# USB_Sheet.net
KiCad netlist of a schematic drawn in Altium Designer
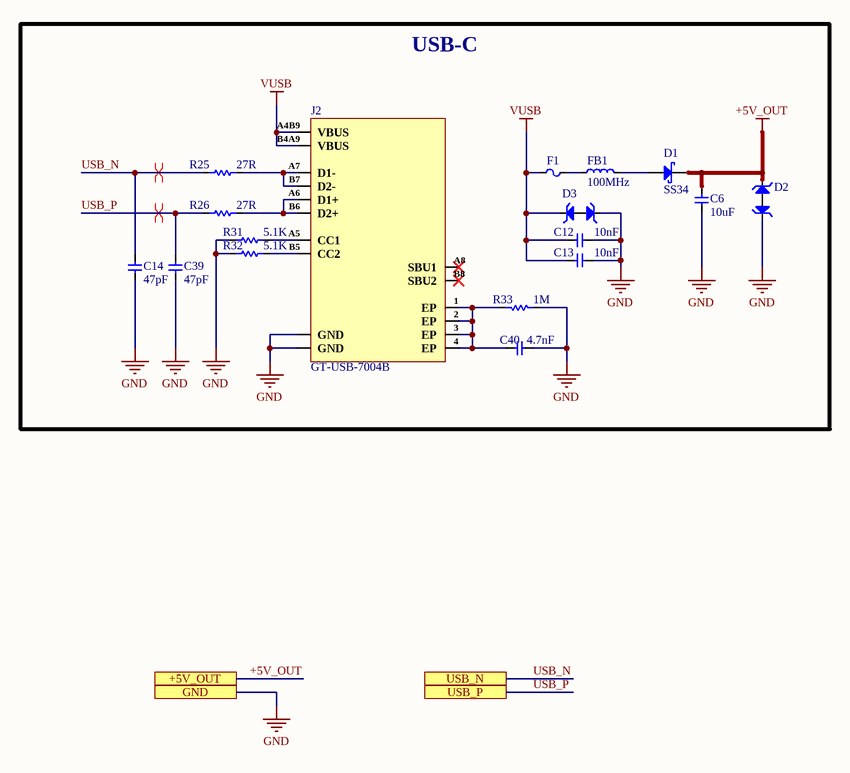
[diagram p0: USB_Sheet.SchDoc]

(export (version "E")
  (design (tool "Eeschema 10.0.6"))
  (components
    (comp (ref "C6")
      (value "10uF")
      (footprint "Cap-0603")
      (description "CAP CER 10UF 25V X5R 0603")
      (fields
        (field (name "MANUFACTURER") "Samsung")
        (field (name "MANUFACTURER PART NUMBER") "CL10A106MA8NRNC")
      )
      (libsource (lib "eSpark Libraries") (part "CL10A106MA8NRNC"))
    )
    (comp (ref "C12")
      (value "10nF")
      (footprint "Cap-0402")
      (description "CAP CER 10000PF 25V X7R 0402")
      (fields
        (field (name "MANUFACTURER") "Yageo")
        (field (name "MANUFACTURER PART NUMBER") "CC0402KRX7R8BB103")
      )
      (libsource (lib "eSpark Libraries") (part "CC0402KRX7R8BB103"))
    )
    (comp (ref "C13")
      (value "10nF")
      (footprint "Cap-0402")
      (description "CAP CER 10000PF 25V X7R 0402")
      (fields
        (field (name "MANUFACTURER") "Yageo")
        (field (name "MANUFACTURER PART NUMBER") "CC0402KRX7R8BB103")
      )
      (libsource (lib "eSpark Libraries") (part "CC0402KRX7R8BB103"))
    )
    (comp (ref "C14")
      (value "47pF")
      (footprint "Cap-0402")
      (description "CAP CER 47PF 50V C0G/NP0 0402")
      (fields
        (field (name "MANUFACTURER") "Murata")
        (field (name "MANUFACTURER PART NUMBER") "GCM1555C1H470FA16D")
      )
      (libsource (lib "eSpark Libraries") (part "GCM1555C1H470FA16D"))
    )
    (comp (ref "C39")
      (value "47pF")
      (footprint "Cap-0402")
      (description "CAP CER 47PF 50V C0G/NP0 0402")
      (fields
        (field (name "MANUFACTURER") "Murata")
        (field (name "MANUFACTURER PART NUMBER") "GCM1555C1H470FA16D")
      )
      (libsource (lib "eSpark Libraries") (part "GCM1555C1H470FA16D"))
    )
    (comp (ref "C40")
      (value "4.7nF")
      (footprint "Cap-0402")
      (description "CAP CER 4700PF 50V X7R 0402")
      (fields
        (field (name "MANUFACTURER") "Yageo")
        (field (name "MANUFACTURER PART NUMBER") "CC0402KRX7R9BB472")
      )
      (libsource (lib "eSpark Libraries") (part "CC0402KRX7R9BB472"))
    )
    (comp (ref "D1")
      (value "SS34")
      (footprint "SMA")
      (description "0.5mA@40V 40V Single 3A 0.55V@3A SMA(DO-214AC) Schottky Barrier Diodes (SBD) ROHS")
      (fields (field (name "MANUFACTURER") "MDD") (field (name "LCSC PART NUMBER") "C8678"))
      (libsource (lib "eSpark Libraries") (part "SS34"))
    )
    (comp (ref "D2")
      (value "PESD5V0H1BSFYL")
      (footprint "DSN0603-2")
      (description "TVS DIODE 5VWM 6.3VC DSN0603-2")
      (fields (field (name "MANUFACTURER") "Nexperia") (field (name "LCSC PART NUMBER") "C477989"))
      (libsource (lib "eSpark Libraries") (part "PESD5V0H1BSFYL"))
    )
    (comp (ref "D3")
      (value "PESD5V0H1BSFYL")
      (footprint "DSN0603-2")
      (description "TVS DIODE 5VWM 6.3VC DSN0603-2")
      (fields (field (name "MANUFACTURER") "Nexperia") (field (name "LCSC PART NUMBER") "C477989"))
      (libsource (lib "eSpark Libraries") (part "PESD5V0H1BSFYL"))
    )
    (comp (ref "F1")
      (value "BSMD0805L-300")
      (footprint "Fuse-0805")
      (description "6V 3A 50A 1W -40℃~+85℃ 6A 3mΩ 5s 30mΩ 0805 Resettable Fuses ROHS")
      (fields (field (name "MANUFACTURER") "BHFUSE") (field (name "LCSC PART NUMBER") "C2757932"))
      (libsource (lib "eSpark Libraries") (part "BSMD0805L-300"))
    )
    (comp (ref "FB1")
      (value "100MHz")
      (footprint "IND-1206")
      (description "FERRITE BEAD 120 OHM 1206 1LN")
      (fields
        (field (name "MANUFACTURER") "Murata")
        (field (name "MANUFACTURER PART NUMBER") "BLM31PG121SN1L")
      )
      (libsource (lib "eSpark Libraries") (part "BLM31PG121SN1L"))
    )
    (comp (ref "J2")
      (value "GT-USB-7004B")
      (footprint "GT-USB-7004B")
      (description "USB-C (USB TYPE-C) Receptacle Connector 16 Position Surface Mount, Right Angle")
      (fields (field (name "MANUFACTURER") "G-Switch") (field (name "LCSC PART NUMBER") "C5368946"))
      (libsource (lib "eSpark Libraries") (part "GT-USB-7004B"))
    )
    (comp (ref "R25")
      (value "27R")
      (footprint "Res-0402")
      (description "62.5mW Thick Film Resistors 50V ±100ppm/℃ ±1% 27Ω 0402 Chip Resistor - Surface Mount ROHS")
      (fields
        (field (name "MANUFACTURER") "YAGEO")
        (field (name "MANUFACTURER PART NUMBER") "RC0402FR-0727RL")
      )
      (libsource (lib "eSpark Libraries") (part "RC0402FR-0727RL"))
    )
    (comp (ref "R26")
      (value "27R")
      (footprint "Res-0402")
      (description "62.5mW Thick Film Resistors 50V ±100ppm/℃ ±1% 27Ω 0402 Chip Resistor - Surface Mount ROHS")
      (fields
        (field (name "MANUFACTURER") "YAGEO")
        (field (name "MANUFACTURER PART NUMBER") "RC0402FR-0727RL")
      )
      (libsource (lib "eSpark Libraries") (part "RC0402FR-0727RL"))
    )
    (comp (ref "R31")
      (value "5.1K")
      (footprint "Res-0402")
      (description "RES 5.1K OHM 1% 1/16W 0402")
      (fields
        (field (name "MANUFACTURER") "Yageo")
        (field (name "MANUFACTURER PART NUMBER") "RC0402FR-075K1L")
      )
      (libsource (lib "eSpark Libraries") (part "RC0402FR-075K1L"))
    )
    (comp (ref "R32")
      (value "5.1K")
      (footprint "Res-0402")
      (description "RES 5.1K OHM 1% 1/16W 0402")
      (fields
        (field (name "MANUFACTURER") "Yageo")
        (field (name "MANUFACTURER PART NUMBER") "RC0402FR-075K1L")
      )
      (libsource (lib "eSpark Libraries") (part "RC0402FR-075K1L"))
    )
    (comp (ref "R33")
      (value "1M")
      (footprint "Res-0402")
      (description "RES SMD 1M OHM 5% 1/16W 0402")
      (fields
        (field (name "MANUFACTURER") "Yageo")
        (field (name "MANUFACTURER PART NUMBER") "AF0402JR-071ML")
      )
      (libsource (lib "eSpark Libraries") (part "AF0402JR-071ML"))
    )
  )
  (nets
    (net (code "1") (name "+5V_OUT") (class "Default")
      (node (ref "C6") (pin "2") (pinfunction "2_2") (pintype "passive"))
      (node (ref "D1") (pin "1") (pinfunction "K_1") (pintype "passive"))
      (node (ref "D2") (pin "2") (pinfunction "2_2") (pintype "passive"))
    )
    (net (code "2") (name "/USB_N") (class "Default")
      (node (ref "C14") (pin "2") (pinfunction "2_2") (pintype "passive"))
      (node (ref "R25") (pin "1") (pinfunction "1_1") (pintype "passive"))
    )
    (net (code "3") (name "/USB_P") (class "Default")
      (node (ref "C39") (pin "2") (pinfunction "2_2") (pintype "passive"))
      (node (ref "R26") (pin "1") (pinfunction "1_1") (pintype "passive"))
    )
    (net (code "4") (name "GND") (class "Default")
      (node (ref "C12") (pin "2") (pinfunction "2_2") (pintype "passive"))
      (node (ref "C13") (pin "2") (pinfunction "2_2") (pintype "passive"))
      (node (ref "C14") (pin "1") (pinfunction "1_1") (pintype "passive"))
      (node (ref "C39") (pin "1") (pinfunction "1_1") (pintype "passive"))
      (node (ref "C40") (pin "1") (pinfunction "1_1") (pintype "passive"))
      (node (ref "C6") (pin "1") (pinfunction "1_1") (pintype "passive"))
      (node (ref "D2") (pin "1") (pinfunction "1_1") (pintype "passive"))
      (node (ref "D3") (pin "2") (pinfunction "2_2") (pintype "passive"))
      (node (ref "J2") (pin "A1B12") (pinfunction "GND_A1B12") (pintype "passive"))
      (node (ref "J2") (pin "B1A12") (pinfunction "GND_B1A12") (pintype "passive"))
      (node (ref "R31") (pin "1") (pinfunction "1_1") (pintype "passive"))
      (node (ref "R32") (pin "1") (pinfunction "1_1") (pintype "passive"))
      (node (ref "R33") (pin "1") (pinfunction "1_1") (pintype "passive"))
    )
    (net (code "5") (name "Net-(C40-Pad2)") (class "Default")
      (node (ref "C40") (pin "2") (pinfunction "2_2") (pintype "passive"))
      (node (ref "J2") (pin "1") (pinfunction "EP_1") (pintype "passive"))
      (node (ref "J2") (pin "2") (pinfunction "EP_2") (pintype "passive"))
      (node (ref "J2") (pin "3") (pinfunction "EP_3") (pintype "passive"))
      (node (ref "J2") (pin "4") (pinfunction "EP_4") (pintype "passive"))
      (node (ref "R33") (pin "2") (pinfunction "2_2") (pintype "passive"))
    )
    (net (code "6") (name "Net-(D1-A)") (class "Default")
      (node (ref "D1") (pin "2") (pinfunction "A_2") (pintype "passive"))
      (node (ref "FB1") (pin "2") (pinfunction "2_2") (pintype "passive"))
    )
    (net (code "7") (name "Net-(F1-Pad2)") (class "Default")
      (node (ref "F1") (pin "2") (pinfunction "2_2") (pintype "passive"))
      (node (ref "FB1") (pin "1") (pinfunction "1_1") (pintype "passive"))
    )
    (net (code "8") (name "Net-(J2-CC1)") (class "Default")
      (node (ref "J2") (pin "A5") (pinfunction "CC1_A5") (pintype "passive"))
      (node (ref "R31") (pin "2") (pinfunction "2_2") (pintype "passive"))
    )
    (net (code "9") (name "Net-(J2-CC2)") (class "Default")
      (node (ref "J2") (pin "B5") (pinfunction "CC2_B5") (pintype "passive"))
      (node (ref "R32") (pin "2") (pinfunction "2_2") (pintype "passive"))
    )
    (net (code "10") (name "Net-(J2-D1+)") (class "Default")
      (node (ref "J2") (pin "A6") (pinfunction "D1+_A6") (pintype "passive"))
      (node (ref "J2") (pin "B6") (pinfunction "D2+_B6") (pintype "passive"))
      (node (ref "R26") (pin "2") (pinfunction "2_2") (pintype "passive"))
    )
    (net (code "11") (name "Net-(J2-D1-)") (class "Default")
      (node (ref "J2") (pin "A7") (pinfunction "D1-_A7") (pintype "passive"))
      (node (ref "J2") (pin "B7") (pinfunction "D2-_B7") (pintype "passive"))
      (node (ref "R25") (pin "2") (pinfunction "2_2") (pintype "passive"))
    )
    (net (code "12") (name "VUSB") (class "Default")
      (node (ref "C12") (pin "1") (pinfunction "1_1") (pintype "passive"))
      (node (ref "C13") (pin "1") (pinfunction "1_1") (pintype "passive"))
      (node (ref "D3") (pin "1") (pinfunction "1_1") (pintype "passive"))
      (node (ref "F1") (pin "1") (pinfunction "1_1") (pintype "passive"))
      (node (ref "J2") (pin "A4B9") (pinfunction "VBUS_A4B9") (pintype "passive"))
      (node (ref "J2") (pin "B4A9") (pinfunction "VBUS_B4A9") (pintype "passive"))
    )
    (net (code "13") (name "unconnected-(J2-SBU1-PadA8)") (class "Default")
      (node (ref "J2") (pin "A8") (pinfunction "SBU1_A8") (pintype "passive+no_connect"))
    )
    (net (code "14") (name "unconnected-(J2-SBU2-PadB8)") (class "Default")
      (node (ref "J2") (pin "B8") (pinfunction "SBU2_B8") (pintype "passive+no_connect"))
    )
  )
)
